# RFM22_Shield-v10.net
KiCad netlist of a schematic drawn in EAGLE
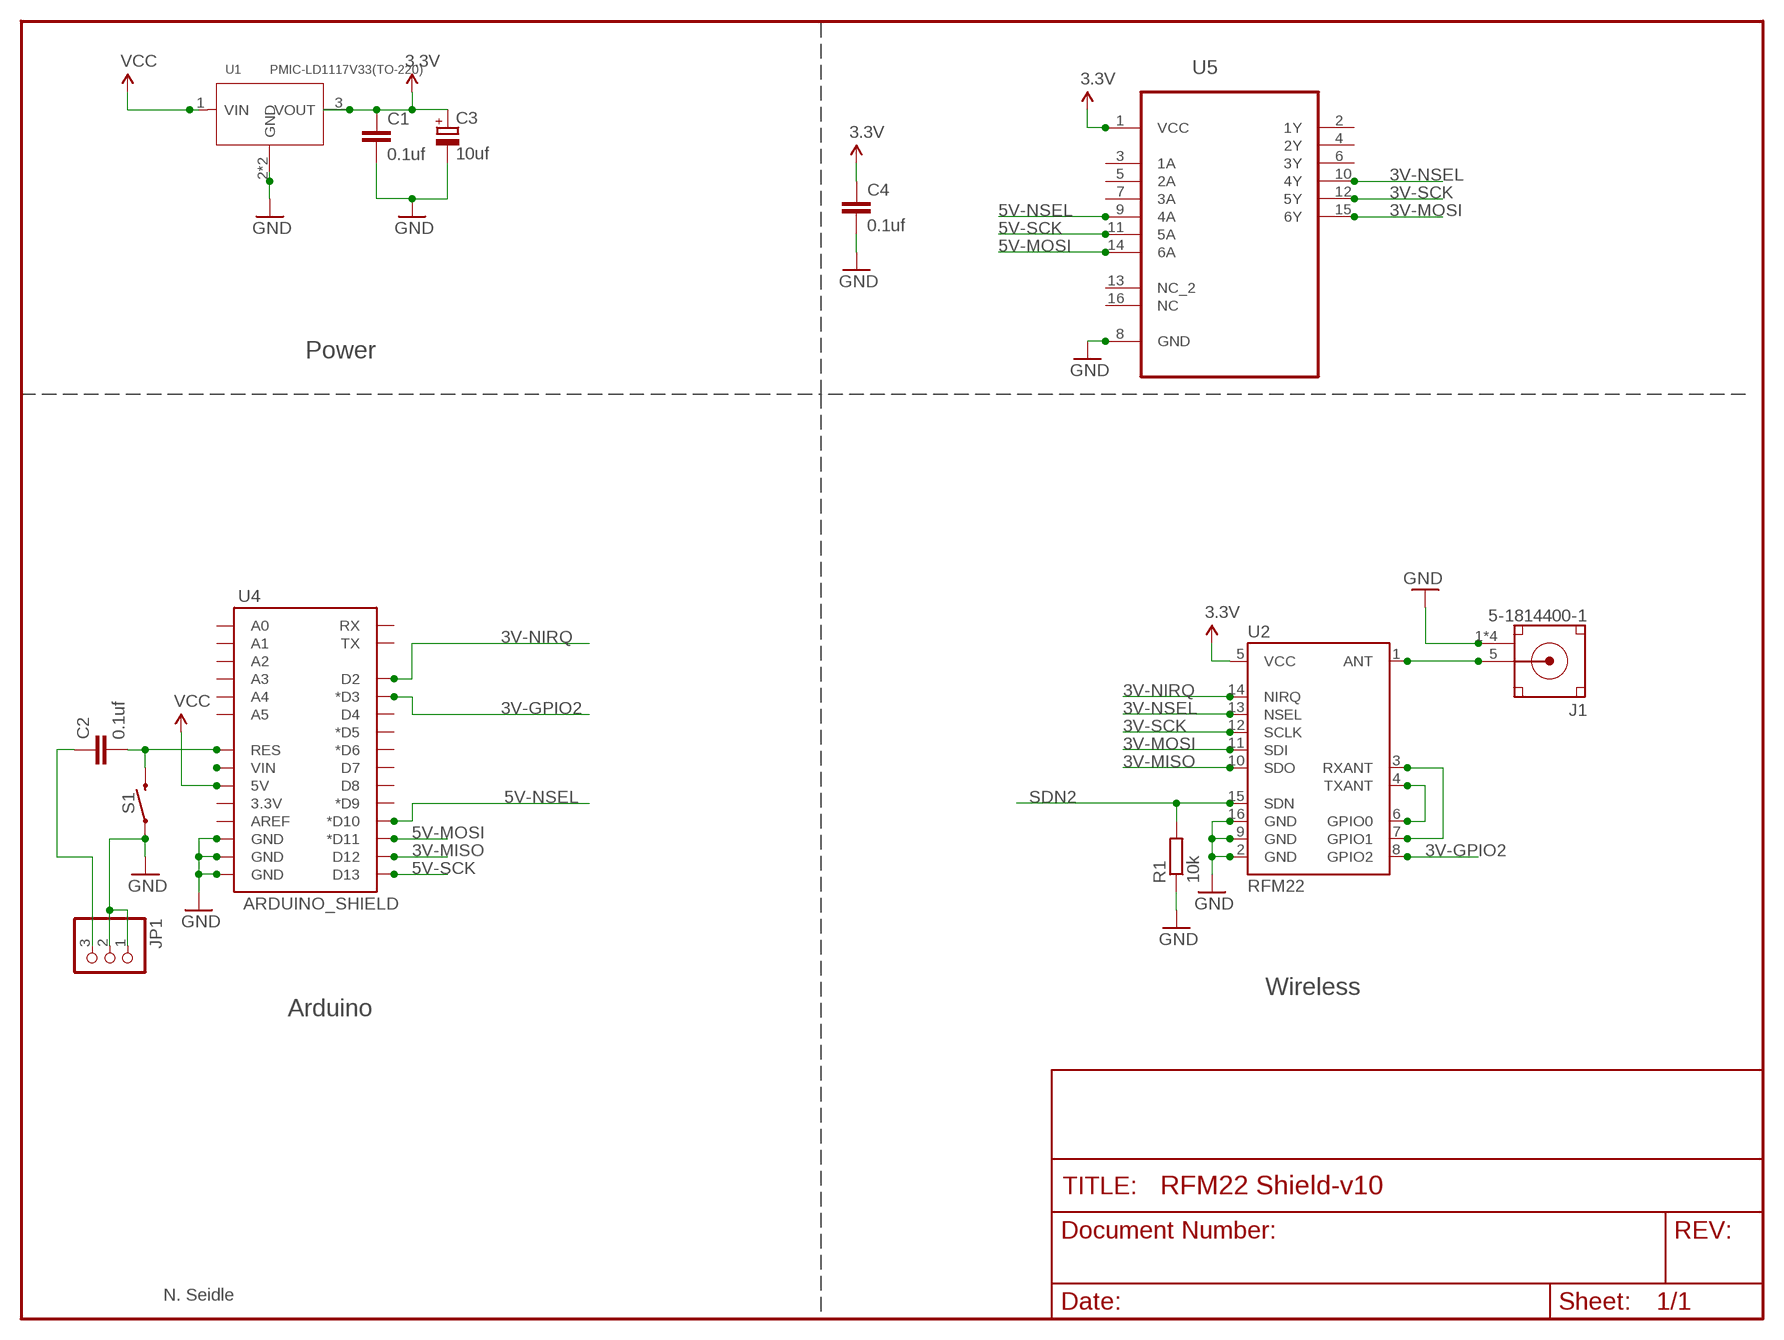
[diagram p0: schematic, sheet 1]

(export (version "E")
  (design (tool "Eeschema 10.0.6"))
  (components
    (comp (ref "C1")
      (value "0.1uf")
      (footprint "eagle-import:C050-030X075")
      (libsource (lib "eagle-import") (part "C-EU050-030X075"))
    )
    (comp (ref "C2")
      (value "0.1uf")
      (footprint "eagle-import:C050-030X075")
      (libsource (lib "eagle-import") (part "C-EU050-030X075"))
    )
    (comp (ref "C3")
      (value "10uf")
      (footprint "eagle-import:E5-8,5")
      (libsource (lib "eagle-import") (part "CPOL-EUE5-8.5"))
    )
    (comp (ref "C4")
      (value "0.1uf")
      (footprint "eagle-import:C050-030X075")
      (libsource (lib "eagle-import") (part "C-EU050-030X075"))
    )
    (comp (ref "J1")
      (value "5-1814400-1")
      (footprint "eagle-import:CONN_5-1814400-1")
      (fields (field (name "MF") "TE Connectivity"))
      (libsource (lib "eagle-import") (part "5-1814400-1"))
    )
    (comp (ref "JP1")
      (value "PINHD-1X3")
      (footprint "eagle-import:1X03")
      (libsource (lib "eagle-import") (part "PINHD-1X3"))
    )
    (comp (ref "R1")
      (value "10k")
      (footprint "eagle-import:0207_10")
      (libsource (lib "eagle-import") (part "R-EU_0207/10"))
    )
    (comp (ref "S1")
      (value "MOMENTARY-SWITCH-SPST-PTH-6.0MM")
      (footprint "eagle-import:TACTILE_SWITCH_PTH_6.0MM")
      (libsource (lib "eagle-import") (part "MOMENTARY-SWITCH-SPST-PTH-6.0MM"))
    )
    (comp (ref "U1")
      (value "PMIC-LD1117V33(TO-220)")
      (footprint "eagle-import:TO-220")
      (fields (field (name "MF") "STMicroelectronics") (field (name "MP") "LD1117V33"))
      (libsource (lib "eagle-import") (part "PMIC-LD1117V33(TO-220)"))
    )
    (comp (ref "U2")
      (value "RFM22")
      (footprint "eagle-import:RFM22-XXX-S2")
      (libsource (lib "eagle-import") (part "RFM22SMD"))
    )
    (comp (ref "U4")
      (value "ARDUINO_SHIELD")
      (footprint "eagle-import:DUEMILANOVE_SHIELD_NOHOLES")
      (libsource (lib "eagle-import") (part "ARDUINO_SHIELDNOHOLES"))
    )
    (comp (ref "U5")
      (value "74HC4050N,652")
      (footprint "eagle-import:DIP254P762X420-16")
      (fields (field (name "MF") "NXP Semiconductors"))
      (libsource (lib "eagle-import") (part "74HC4050N,652"))
    )
  )
  (nets
    (net (code "1") (name "/3V-GPIO2") (class "Default")
      (node (ref "U2") (pin "8") (pinfunction "GPIO2_8") (pintype "bidirectional"))
      (node (ref "U4") (pin "D3") (pinfunction "*D3_D3") (pintype "bidirectional"))
    )
    (net (code "2") (name "/3V-MISO") (class "Default")
      (node (ref "U2") (pin "10") (pinfunction "SDO_10") (pintype "output"))
      (node (ref "U4") (pin "D12") (pinfunction "D12_D12") (pintype "bidirectional"))
    )
    (net (code "3") (name "/3V-MOSI") (class "Default")
      (node (ref "U2") (pin "11") (pinfunction "SDI_11") (pintype "input"))
      (node (ref "U5") (pin "15") (pinfunction "6Y_15") (pintype "output"))
    )
    (net (code "4") (name "/3V-NIRQ") (class "Default")
      (node (ref "U2") (pin "14") (pinfunction "NIRQ_14") (pintype "output"))
      (node (ref "U4") (pin "D2") (pinfunction "D2_D2") (pintype "bidirectional"))
    )
    (net (code "5") (name "/3V-NSEL") (class "Default")
      (node (ref "U2") (pin "13") (pinfunction "NSEL_13") (pintype "input"))
      (node (ref "U5") (pin "10") (pinfunction "4Y_10") (pintype "output"))
    )
    (net (code "6") (name "/3V-SCK") (class "Default")
      (node (ref "U2") (pin "12") (pinfunction "SCLK_12") (pintype "input"))
      (node (ref "U5") (pin "12") (pinfunction "5Y_12") (pintype "output"))
    )
    (net (code "7") (name "/5V-MOSI") (class "Default")
      (node (ref "U4") (pin "D11") (pinfunction "*D11_D11") (pintype "bidirectional"))
      (node (ref "U5") (pin "14") (pinfunction "6A_14") (pintype "input"))
    )
    (net (code "8") (name "/5V-NSEL") (class "Default")
      (node (ref "U4") (pin "D10") (pinfunction "*D10_D10") (pintype "bidirectional"))
      (node (ref "U5") (pin "9") (pinfunction "4A_9") (pintype "input"))
    )
    (net (code "9") (name "/5V-SCK") (class "Default")
      (node (ref "U4") (pin "D13") (pinfunction "D13_D13") (pintype "bidirectional"))
      (node (ref "U5") (pin "11") (pinfunction "5A_11") (pintype "input"))
    )
    (net (code "10") (name "/SDN2") (class "Default")
      (node (ref "R1") (pin "2") (pinfunction "2_2") (pintype "passive"))
      (node (ref "U2") (pin "15") (pinfunction "SDN_15") (pintype "input"))
    )
    (net (code "11") (name "3.3V") (class "Default")
      (node (ref "C1") (pin "1") (pinfunction "1_1") (pintype "passive"))
      (node (ref "C3") (pin "+") (pinfunction "+_+") (pintype "passive"))
      (node (ref "C4") (pin "1") (pinfunction "1_1") (pintype "passive"))
      (node (ref "U1") (pin "3") (pinfunction "VOUT_3") (pintype "bidirectional"))
      (node (ref "U2") (pin "5") (pinfunction "VCC_5") (pintype "bidirectional"))
      (node (ref "U5") (pin "1") (pinfunction "VCC_1") (pintype "power_in"))
    )
    (net (code "12") (name "GND") (class "Default")
      (node (ref "C1") (pin "2") (pinfunction "2_2") (pintype "passive"))
      (node (ref "C3") (pin "-") (pinfunction "-_-") (pintype "passive"))
      (node (ref "C4") (pin "2") (pinfunction "2_2") (pintype "passive"))
      (node (ref "J1") (pin "1") (pinfunction "GND_1") (pintype "power_in"))
      (node (ref "J1") (pin "2") (pinfunction "GND_2") (pintype "power_in"))
      (node (ref "J1") (pin "3") (pinfunction "GND_3") (pintype "power_in"))
      (node (ref "J1") (pin "4") (pinfunction "GND_4") (pintype "power_in"))
      (node (ref "JP1") (pin "1") (pinfunction "1_1") (pintype "passive"))
      (node (ref "JP1") (pin "2") (pinfunction "2_2") (pintype "passive"))
      (node (ref "R1") (pin "1") (pinfunction "1_1") (pintype "passive"))
      (node (ref "S1") (pin "1") (pinfunction "1_1") (pintype "passive"))
      (node (ref "U1") (pin "2") (pinfunction "GND_2") (pintype "bidirectional"))
      (node (ref "U1") (pin "HEAT") (pinfunction "GND_HEAT") (pintype "bidirectional"))
      (node (ref "U2") (pin "16") (pinfunction "GND_16") (pintype "power_in"))
      (node (ref "U2") (pin "2") (pinfunction "GND_2") (pintype "power_in"))
      (node (ref "U2") (pin "9") (pinfunction "GND_9") (pintype "power_in"))
      (node (ref "U4") (pin "GND@0") (pinfunction "GND_GND@0") (pintype "bidirectional"))
      (node (ref "U4") (pin "GND@1") (pinfunction "GND_GND@1") (pintype "bidirectional"))
      (node (ref "U4") (pin "GND@2") (pinfunction "GND_GND@2") (pintype "bidirectional"))
      (node (ref "U5") (pin "8") (pinfunction "GND_8") (pintype "passive"))
    )
    (net (code "13") (name "Net-(C2-Pad1)") (class "Default")
      (node (ref "C2") (pin "1") (pinfunction "1_1") (pintype "passive"))
      (node (ref "JP1") (pin "3") (pinfunction "3_3") (pintype "passive"))
    )
    (net (code "14") (name "Net-(J1-SIGNAL)") (class "Default")
      (node (ref "J1") (pin "5") (pinfunction "SIGNAL_5") (pintype "passive"))
      (node (ref "U2") (pin "1") (pinfunction "ANT_1") (pintype "bidirectional"))
    )
    (net (code "15") (name "Net-(S1-2)") (class "Default")
      (node (ref "C2") (pin "2") (pinfunction "2_2") (pintype "passive"))
      (node (ref "S1") (pin "3") (pinfunction "2_3") (pintype "passive"))
      (node (ref "U4") (pin "RES") (pinfunction "RES_RES") (pintype "bidirectional"))
    )
    (net (code "16") (name "Net-(U2-GPIO0)") (class "Default")
      (node (ref "U2") (pin "4") (pinfunction "TXANT_4") (pintype "input"))
      (node (ref "U2") (pin "6") (pinfunction "GPIO0_6") (pintype "bidirectional"))
    )
    (net (code "17") (name "Net-(U2-GPIO1)") (class "Default")
      (node (ref "U2") (pin "3") (pinfunction "RXANT_3") (pintype "input"))
      (node (ref "U2") (pin "7") (pinfunction "GPIO1_7") (pintype "bidirectional"))
    )
    (net (code "18") (name "VCC") (class "Default")
      (node (ref "U1") (pin "1") (pinfunction "VIN_1") (pintype "bidirectional"))
      (node (ref "U4") (pin "5V") (pinfunction "5V_5V") (pintype "bidirectional"))
    )
    (net (code "19") (name "unconnected-(U4-*D5-PadD5)") (class "Default")
      (node (ref "U4") (pin "D5") (pinfunction "*D5_D5") (pintype "bidirectional"))
    )
    (net (code "20") (name "unconnected-(U4-*D6-PadD6)") (class "Default")
      (node (ref "U4") (pin "D6") (pinfunction "*D6_D6") (pintype "bidirectional"))
    )
    (net (code "21") (name "unconnected-(U4-*D9-PadD9)") (class "Default")
      (node (ref "U4") (pin "D9") (pinfunction "*D9_D9") (pintype "bidirectional"))
    )
    (net (code "22") (name "unconnected-(U4-Pad3.3V)") (class "Default")
      (node (ref "U4") (pin "3.3V") (pinfunction "3.3V_3.3V") (pintype "bidirectional"))
    )
    (net (code "23") (name "unconnected-(U4-PadA0)") (class "Default")
      (node (ref "U4") (pin "A0") (pinfunction "A0_A0") (pintype "bidirectional"))
    )
    (net (code "24") (name "unconnected-(U4-PadA1)") (class "Default")
      (node (ref "U4") (pin "A1") (pinfunction "A1_A1") (pintype "bidirectional"))
    )
    (net (code "25") (name "unconnected-(U4-PadA2)") (class "Default")
      (node (ref "U4") (pin "A2") (pinfunction "A2_A2") (pintype "bidirectional"))
    )
    (net (code "26") (name "unconnected-(U4-PadA3)") (class "Default")
      (node (ref "U4") (pin "A3") (pinfunction "A3_A3") (pintype "bidirectional"))
    )
    (net (code "27") (name "unconnected-(U4-PadA4)") (class "Default")
      (node (ref "U4") (pin "A4") (pinfunction "A4_A4") (pintype "bidirectional"))
    )
    (net (code "28") (name "unconnected-(U4-PadA5)") (class "Default")
      (node (ref "U4") (pin "A5") (pinfunction "A5_A5") (pintype "bidirectional"))
    )
    (net (code "29") (name "unconnected-(U4-PadAREF)") (class "Default")
      (node (ref "U4") (pin "AREF") (pinfunction "AREF_AREF") (pintype "bidirectional"))
    )
    (net (code "30") (name "unconnected-(U4-PadD4)") (class "Default")
      (node (ref "U4") (pin "D4") (pinfunction "D4_D4") (pintype "bidirectional"))
    )
    (net (code "31") (name "unconnected-(U4-PadD7)") (class "Default")
      (node (ref "U4") (pin "D7") (pinfunction "D7_D7") (pintype "bidirectional"))
    )
    (net (code "32") (name "unconnected-(U4-PadD8)") (class "Default")
      (node (ref "U4") (pin "D8") (pinfunction "D8_D8") (pintype "bidirectional"))
    )
    (net (code "33") (name "unconnected-(U4-PadRX)") (class "Default")
      (node (ref "U4") (pin "RX") (pinfunction "RX_RX") (pintype "bidirectional"))
    )
    (net (code "34") (name "unconnected-(U4-PadTX)") (class "Default")
      (node (ref "U4") (pin "TX") (pinfunction "TX_TX") (pintype "bidirectional"))
    )
    (net (code "35") (name "unconnected-(U4-PadVIN)") (class "Default")
      (node (ref "U4") (pin "VIN") (pinfunction "VIN_VIN") (pintype "bidirectional"))
    )
    (net (code "36") (name "unconnected-(U5-1A-Pad3)") (class "Default")
      (node (ref "U5") (pin "3") (pinfunction "1A_3") (pintype "input"))
    )
    (net (code "37") (name "unconnected-(U5-1Y-Pad2)") (class "Default")
      (node (ref "U5") (pin "2") (pinfunction "1Y_2") (pintype "output"))
    )
    (net (code "38") (name "unconnected-(U5-2A-Pad5)") (class "Default")
      (node (ref "U5") (pin "5") (pinfunction "2A_5") (pintype "input"))
    )
    (net (code "39") (name "unconnected-(U5-2Y-Pad4)") (class "Default")
      (node (ref "U5") (pin "4") (pinfunction "2Y_4") (pintype "output"))
    )
    (net (code "40") (name "unconnected-(U5-3A-Pad7)") (class "Default")
      (node (ref "U5") (pin "7") (pinfunction "3A_7") (pintype "input"))
    )
    (net (code "41") (name "unconnected-(U5-3Y-Pad6)") (class "Default")
      (node (ref "U5") (pin "6") (pinfunction "3Y_6") (pintype "output"))
    )
    (net (code "42") (name "unconnected-(U5-NC-Pad16)") (class "Default")
      (node (ref "U5") (pin "16") (pinfunction "NC_16") (pintype "no_connect"))
    )
    (net (code "43") (name "unconnected-(U5-NC_2-Pad13)") (class "Default")
      (node (ref "U5") (pin "13") (pinfunction "NC_2_13") (pintype "no_connect"))
    )
  )
)
